# escon-50-5-mobo.net
KiCad netlist of a schematic drawn in EAGLE
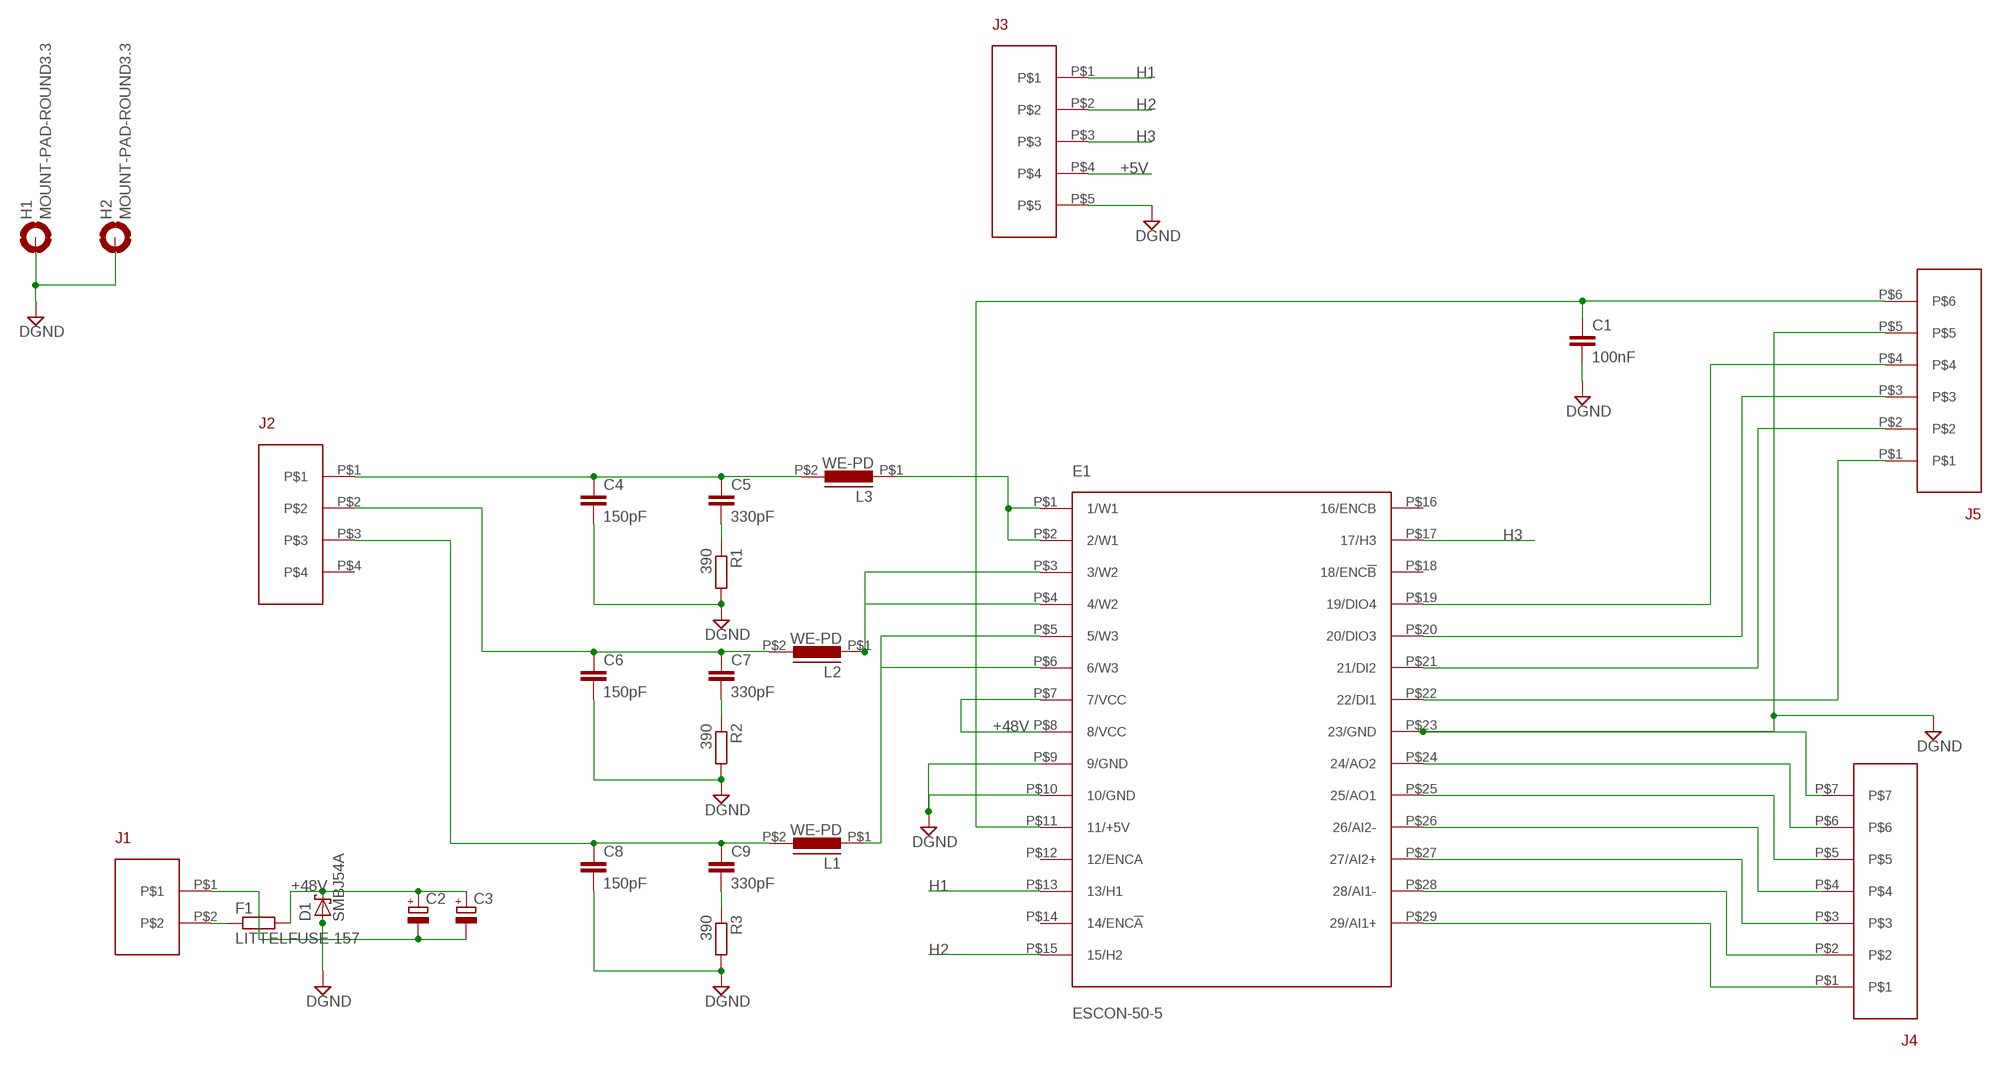
[diagram p0: schematic, sheet 1]

(export (version "E")
  (design (tool "Eeschema 10.0.6"))
  (components
    (comp (ref "C1")
      (value "100nF")
      (footprint "eagle-import:C0805")
      (libsource (lib "eagle-import") (part "C-EUC0805"))
    )
    (comp (ref "C2")
      (value "CPOL-EUE5-13")
      (footprint "eagle-import:E5-13")
      (libsource (lib "eagle-import") (part "CPOL-EUE5-13"))
    )
    (comp (ref "C3")
      (value "CPOL-EUE5-13")
      (footprint "eagle-import:E5-13")
      (libsource (lib "eagle-import") (part "CPOL-EUE5-13"))
    )
    (comp (ref "C4")
      (value "150pF")
      (footprint "eagle-import:C0805")
      (libsource (lib "eagle-import") (part "C-EUC0805"))
    )
    (comp (ref "C5")
      (value "330pF")
      (footprint "eagle-import:C0805")
      (libsource (lib "eagle-import") (part "C-EUC0805"))
    )
    (comp (ref "C6")
      (value "150pF")
      (footprint "eagle-import:C0805")
      (libsource (lib "eagle-import") (part "C-EUC0805"))
    )
    (comp (ref "C7")
      (value "330pF")
      (footprint "eagle-import:C0805")
      (libsource (lib "eagle-import") (part "C-EUC0805"))
    )
    (comp (ref "C8")
      (value "150pF")
      (footprint "eagle-import:C0805")
      (libsource (lib "eagle-import") (part "C-EUC0805"))
    )
    (comp (ref "C9")
      (value "330pF")
      (footprint "eagle-import:C0805")
      (libsource (lib "eagle-import") (part "C-EUC0805"))
    )
    (comp (ref "D1")
      (value "SMBJ54A")
      (footprint "eagle-import:SMBJ54A")
      (libsource (lib "eagle-import") (part "SMBJ54A"))
    )
    (comp (ref "E1")
      (value "ESCON-50-5")
      (footprint "eagle-import:ESCON-50-5")
      (libsource (lib "eagle-import") (part "ESCON-50-5"))
    )
    (comp (ref "F1")
      (value "LITTELFUSE-157")
      (footprint "eagle-import:LITTELFUSE-157")
      (libsource (lib "eagle-import") (part "LITTELFUSE-157"))
    )
    (comp (ref "H1")
      (value "MOUNT-PAD-ROUND3.3")
      (footprint "eagle-import:3,3-PAD")
      (libsource (lib "eagle-import") (part "MOUNT-PAD-ROUND3.3"))
    )
    (comp (ref "H2")
      (value "MOUNT-PAD-ROUND3.3")
      (footprint "eagle-import:3,3-PAD")
      (libsource (lib "eagle-import") (part "MOUNT-PAD-ROUND3.3"))
    )
    (comp (ref "J1")
      (value "PHOENIX-COMBICON-MCV-2POS")
      (footprint "eagle-import:PHOENIX-COMBICON-MCV-2POS")
      (libsource (lib "eagle-import") (part "PHOENIX-COMBICON-MCV-2POS"))
    )
    (comp (ref "J2")
      (value "PHOENIX-COMBICON-MCV-4POS")
      (footprint "eagle-import:PHOENIX-COMBICON-MCV-4POS")
      (libsource (lib "eagle-import") (part "PHOENIX-COMBICON-MCV-4POS"))
    )
    (comp (ref "J3")
      (value "PHOENIX-COMBICON-MCV-5POS")
      (footprint "eagle-import:PHOENIX-COMBICON-MCV-5POS")
      (libsource (lib "eagle-import") (part "PHOENIX-COMBICON-MCV-5POS"))
    )
    (comp (ref "J4")
      (value "PHOENIX-COMBICON-MCV-7POS")
      (footprint "eagle-import:PHOENIX-COMBICON-MCV-7POS")
      (libsource (lib "eagle-import") (part "PHOENIX-COMBICON-MCV-7POS"))
    )
    (comp (ref "J5")
      (value "PHOENIX-COMBICON-MCV-6POS")
      (footprint "eagle-import:PHOENIX-COMBICON-MCV-6POS")
      (libsource (lib "eagle-import") (part "PHOENIX-COMBICON-MCV-6POS"))
    )
    (comp (ref "L1")
      (value "WE-PD")
      (footprint "eagle-import:WE-PD")
      (libsource (lib "eagle-import") (part "WE-PD"))
    )
    (comp (ref "L2")
      (value "WE-PD")
      (footprint "eagle-import:WE-PD")
      (libsource (lib "eagle-import") (part "WE-PD"))
    )
    (comp (ref "L3")
      (value "WE-PD")
      (footprint "eagle-import:WE-PD")
      (libsource (lib "eagle-import") (part "WE-PD"))
    )
    (comp (ref "R1")
      (value "390")
      (footprint "eagle-import:R0805")
      (libsource (lib "eagle-import") (part "R-EU_R0805"))
    )
    (comp (ref "R2")
      (value "390")
      (footprint "eagle-import:R0805")
      (libsource (lib "eagle-import") (part "R-EU_R0805"))
    )
    (comp (ref "R3")
      (value "390")
      (footprint "eagle-import:R0805")
      (libsource (lib "eagle-import") (part "R-EU_R0805"))
    )
  )
  (nets
    (net (code "1") (name "/+5V") (class "Default")
      (node (ref "C1") (pin "1") (pinfunction "1_1") (pintype "passive"))
      (node (ref "E1") (pin "P$11") (pinfunction "11/+5V_P$11") (pintype "bidirectional"))
      (node (ref "J3") (pin "P$4") (pinfunction "P$4_P$4") (pintype "bidirectional"))
      (node (ref "J5") (pin "P$6") (pinfunction "P$6_P$6") (pintype "bidirectional"))
    )
    (net (code "2") (name "/+48V") (class "Default")
      (node (ref "C2") (pin "+") (pinfunction "+_+") (pintype "passive"))
      (node (ref "C3") (pin "+") (pinfunction "+_+") (pintype "passive"))
      (node (ref "D1") (pin "P$2") (pinfunction "C_P$2") (pintype "passive"))
      (node (ref "E1") (pin "P$7") (pinfunction "7/VCC_P$7") (pintype "bidirectional"))
      (node (ref "E1") (pin "P$8") (pinfunction "8/VCC_P$8") (pintype "bidirectional"))
      (node (ref "F1") (pin "P$2") (pinfunction "2_P$2") (pintype "passive"))
    )
    (net (code "3") (name "/H1") (class "Default")
      (node (ref "E1") (pin "P$13") (pinfunction "13/H1_P$13") (pintype "bidirectional"))
      (node (ref "J3") (pin "P$1") (pinfunction "P$1_P$1") (pintype "bidirectional"))
    )
    (net (code "4") (name "/H2") (class "Default")
      (node (ref "E1") (pin "P$15") (pinfunction "15/H2_P$15") (pintype "bidirectional"))
      (node (ref "J3") (pin "P$2") (pinfunction "P$2_P$2") (pintype "bidirectional"))
    )
    (net (code "5") (name "/H3") (class "Default")
      (node (ref "E1") (pin "P$17") (pinfunction "17/H3_P$17") (pintype "bidirectional"))
      (node (ref "J3") (pin "P$3") (pinfunction "P$3_P$3") (pintype "bidirectional"))
    )
    (net (code "6") (name "DGND") (class "Default")
      (node (ref "C1") (pin "2") (pinfunction "2_2") (pintype "passive"))
      (node (ref "C2") (pin "-") (pinfunction "-_-") (pintype "passive"))
      (node (ref "C3") (pin "-") (pinfunction "-_-") (pintype "passive"))
      (node (ref "C4") (pin "2") (pinfunction "2_2") (pintype "passive"))
      (node (ref "C6") (pin "2") (pinfunction "2_2") (pintype "passive"))
      (node (ref "C8") (pin "2") (pinfunction "2_2") (pintype "passive"))
      (node (ref "D1") (pin "P$1") (pinfunction "A_P$1") (pintype "passive"))
      (node (ref "E1") (pin "P$10") (pinfunction "10/GND_P$10") (pintype "bidirectional"))
      (node (ref "E1") (pin "P$23") (pinfunction "23/GND_P$23") (pintype "bidirectional"))
      (node (ref "E1") (pin "P$9") (pinfunction "9/GND_P$9") (pintype "bidirectional"))
      (node (ref "H1") (pin "B3,3") (pinfunction "MOUNT_B3,3") (pintype "passive"))
      (node (ref "H2") (pin "B3,3") (pinfunction "MOUNT_B3,3") (pintype "passive"))
      (node (ref "J1") (pin "P$1") (pinfunction "P$1_P$1") (pintype "bidirectional"))
      (node (ref "J3") (pin "P$5") (pinfunction "P$5_P$5") (pintype "bidirectional"))
      (node (ref "J4") (pin "P$7") (pinfunction "P$7_P$7") (pintype "bidirectional"))
      (node (ref "J5") (pin "P$5") (pinfunction "P$5_P$5") (pintype "bidirectional"))
      (node (ref "R1") (pin "2") (pinfunction "2_2") (pintype "passive"))
      (node (ref "R2") (pin "2") (pinfunction "2_2") (pintype "passive"))
      (node (ref "R3") (pin "2") (pinfunction "2_2") (pintype "passive"))
    )
    (net (code "7") (name "Net-(C5-Pad2)") (class "Default")
      (node (ref "C5") (pin "2") (pinfunction "2_2") (pintype "passive"))
      (node (ref "R1") (pin "1") (pinfunction "1_1") (pintype "passive"))
    )
    (net (code "8") (name "Net-(C7-Pad2)") (class "Default")
      (node (ref "C7") (pin "2") (pinfunction "2_2") (pintype "passive"))
      (node (ref "R2") (pin "1") (pinfunction "1_1") (pintype "passive"))
    )
    (net (code "9") (name "Net-(C9-Pad2)") (class "Default")
      (node (ref "C9") (pin "2") (pinfunction "2_2") (pintype "passive"))
      (node (ref "R3") (pin "1") (pinfunction "1_1") (pintype "passive"))
    )
    (net (code "10") (name "Net-(E1-1{slash}W1)") (class "Default")
      (node (ref "E1") (pin "P$1") (pinfunction "1/W1_P$1") (pintype "bidirectional"))
      (node (ref "E1") (pin "P$2") (pinfunction "2/W1_P$2") (pintype "bidirectional"))
      (node (ref "L3") (pin "P$1") (pinfunction "1_P$1") (pintype "passive"))
    )
    (net (code "11") (name "Net-(E1-3{slash}W2)") (class "Default")
      (node (ref "E1") (pin "P$3") (pinfunction "3/W2_P$3") (pintype "bidirectional"))
      (node (ref "E1") (pin "P$4") (pinfunction "4/W2_P$4") (pintype "bidirectional"))
      (node (ref "L2") (pin "P$1") (pinfunction "1_P$1") (pintype "passive"))
    )
    (net (code "12") (name "Net-(E1-5{slash}W3)") (class "Default")
      (node (ref "E1") (pin "P$5") (pinfunction "5/W3_P$5") (pintype "bidirectional"))
      (node (ref "E1") (pin "P$6") (pinfunction "6/W3_P$6") (pintype "bidirectional"))
      (node (ref "L1") (pin "P$1") (pinfunction "1_P$1") (pintype "passive"))
    )
    (net (code "13") (name "Net-(E1-19{slash}DIO4)") (class "Default")
      (node (ref "E1") (pin "P$19") (pinfunction "19/DIO4_P$19") (pintype "bidirectional"))
      (node (ref "J5") (pin "P$4") (pinfunction "P$4_P$4") (pintype "bidirectional"))
    )
    (net (code "14") (name "Net-(E1-20{slash}DIO3)") (class "Default")
      (node (ref "E1") (pin "P$20") (pinfunction "20/DIO3_P$20") (pintype "bidirectional"))
      (node (ref "J5") (pin "P$3") (pinfunction "P$3_P$3") (pintype "bidirectional"))
    )
    (net (code "15") (name "Net-(E1-21{slash}DI2)") (class "Default")
      (node (ref "E1") (pin "P$21") (pinfunction "21/DI2_P$21") (pintype "bidirectional"))
      (node (ref "J5") (pin "P$2") (pinfunction "P$2_P$2") (pintype "bidirectional"))
    )
    (net (code "16") (name "Net-(E1-22{slash}DI1)") (class "Default")
      (node (ref "E1") (pin "P$22") (pinfunction "22/DI1_P$22") (pintype "bidirectional"))
      (node (ref "J5") (pin "P$1") (pinfunction "P$1_P$1") (pintype "bidirectional"))
    )
    (net (code "17") (name "Net-(E1-24{slash}AO2)") (class "Default")
      (node (ref "E1") (pin "P$24") (pinfunction "24/AO2_P$24") (pintype "bidirectional"))
      (node (ref "J4") (pin "P$6") (pinfunction "P$6_P$6") (pintype "bidirectional"))
    )
    (net (code "18") (name "Net-(E1-25{slash}AO1)") (class "Default")
      (node (ref "E1") (pin "P$25") (pinfunction "25/AO1_P$25") (pintype "bidirectional"))
      (node (ref "J4") (pin "P$5") (pinfunction "P$5_P$5") (pintype "bidirectional"))
    )
    (net (code "19") (name "Net-(E1-26{slash}AI2-)") (class "Default")
      (node (ref "E1") (pin "P$26") (pinfunction "26/AI2-_P$26") (pintype "bidirectional"))
      (node (ref "J4") (pin "P$4") (pinfunction "P$4_P$4") (pintype "bidirectional"))
    )
    (net (code "20") (name "Net-(E1-27{slash}AI2+)") (class "Default")
      (node (ref "E1") (pin "P$27") (pinfunction "27/AI2+_P$27") (pintype "bidirectional"))
      (node (ref "J4") (pin "P$3") (pinfunction "P$3_P$3") (pintype "bidirectional"))
    )
    (net (code "21") (name "Net-(E1-28{slash}AI1-)") (class "Default")
      (node (ref "E1") (pin "P$28") (pinfunction "28/AI1-_P$28") (pintype "bidirectional"))
      (node (ref "J4") (pin "P$2") (pinfunction "P$2_P$2") (pintype "bidirectional"))
    )
    (net (code "22") (name "Net-(E1-29{slash}AI1+)") (class "Default")
      (node (ref "E1") (pin "P$29") (pinfunction "29/AI1+_P$29") (pintype "bidirectional"))
      (node (ref "J4") (pin "P$1") (pinfunction "P$1_P$1") (pintype "bidirectional"))
    )
    (net (code "23") (name "Net-(F1-1)") (class "Default")
      (node (ref "F1") (pin "P$1") (pinfunction "1_P$1") (pintype "passive"))
      (node (ref "J1") (pin "P$2") (pinfunction "P$2_P$2") (pintype "bidirectional"))
    )
    (net (code "24") (name "Net-(L1-2)") (class "Default")
      (node (ref "C8") (pin "1") (pinfunction "1_1") (pintype "passive"))
      (node (ref "C9") (pin "1") (pinfunction "1_1") (pintype "passive"))
      (node (ref "J2") (pin "P$3") (pinfunction "P$3_P$3") (pintype "bidirectional"))
      (node (ref "L1") (pin "P$2") (pinfunction "2_P$2") (pintype "passive"))
    )
    (net (code "25") (name "Net-(L2-2)") (class "Default")
      (node (ref "C6") (pin "1") (pinfunction "1_1") (pintype "passive"))
      (node (ref "C7") (pin "1") (pinfunction "1_1") (pintype "passive"))
      (node (ref "J2") (pin "P$2") (pinfunction "P$2_P$2") (pintype "bidirectional"))
      (node (ref "L2") (pin "P$2") (pinfunction "2_P$2") (pintype "passive"))
    )
    (net (code "26") (name "Net-(L3-2)") (class "Default")
      (node (ref "C4") (pin "1") (pinfunction "1_1") (pintype "passive"))
      (node (ref "C5") (pin "1") (pinfunction "1_1") (pintype "passive"))
      (node (ref "J2") (pin "P$1") (pinfunction "P$1_P$1") (pintype "bidirectional"))
      (node (ref "L3") (pin "P$2") (pinfunction "2_P$2") (pintype "passive"))
    )
    (net (code "27") (name "unconnected-(E1-12{slash}ENCA-PadP$12)") (class "Default")
      (node (ref "E1") (pin "P$12") (pinfunction "12/ENCA_P$12") (pintype "bidirectional"))
    )
    (net (code "28") (name "unconnected-(E1-14{slash}ENC~{A}-PadP$14)") (class "Default")
      (node (ref "E1") (pin "P$14") (pinfunction "14/ENC~{A}_P$14") (pintype "bidirectional"))
    )
    (net (code "29") (name "unconnected-(E1-16{slash}ENCB-PadP$16)") (class "Default")
      (node (ref "E1") (pin "P$16") (pinfunction "16/ENCB_P$16") (pintype "bidirectional"))
    )
    (net (code "30") (name "unconnected-(E1-18{slash}ENC~{B}-PadP$18)") (class "Default")
      (node (ref "E1") (pin "P$18") (pinfunction "18/ENC~{B}_P$18") (pintype "bidirectional"))
    )
    (net (code "31") (name "unconnected-(J2-PadP$4)") (class "Default")
      (node (ref "J2") (pin "P$4") (pinfunction "P$4_P$4") (pintype "bidirectional"))
    )
  )
)
